# Prototype1.net
KiCad netlist of a schematic drawn in EAGLE
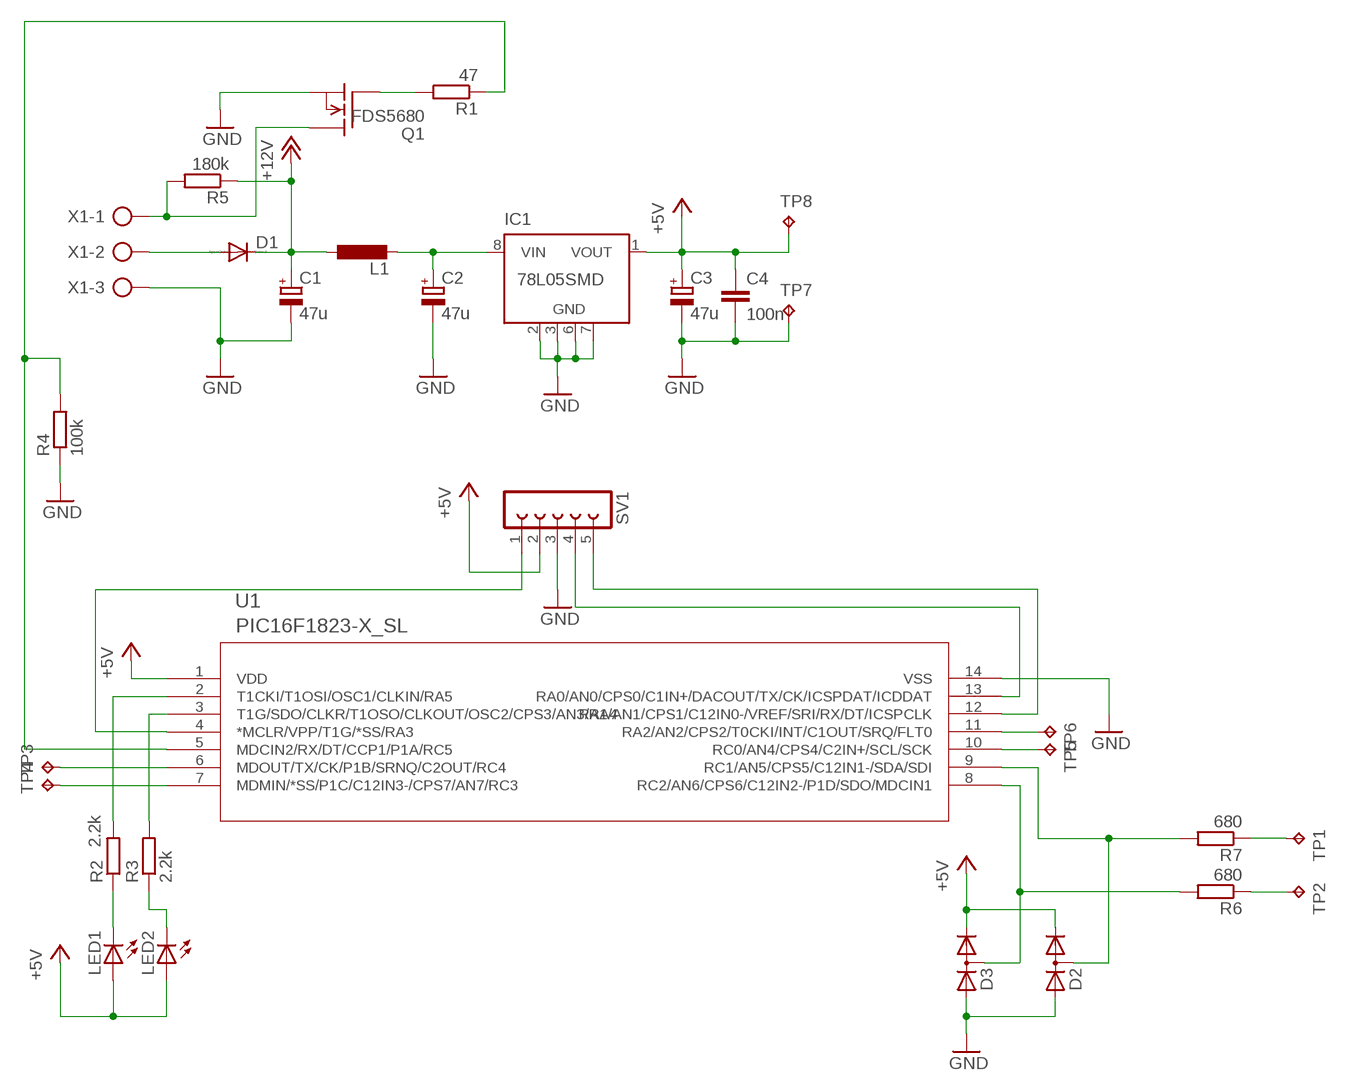
[diagram p0: schematic, sheet 1]

(export (version "E")
  (design (tool "Eeschema 10.0.6"))
  (components
    (comp (ref "C1")
      (value "47u")
      (footprint "eagle-import:153CLV-0605")
      (libsource (lib "eagle-import") (part "CPOL-EU153CLV-0605"))
    )
    (comp (ref "C2")
      (value "47u")
      (footprint "eagle-import:153CLV-0605")
      (libsource (lib "eagle-import") (part "CPOL-EU153CLV-0605"))
    )
    (comp (ref "C3")
      (value "47u")
      (footprint "eagle-import:153CLV-0605")
      (libsource (lib "eagle-import") (part "CPOL-EU153CLV-0605"))
    )
    (comp (ref "C4")
      (value "100n")
      (footprint "eagle-import:C0805")
      (libsource (lib "eagle-import") (part "C-EUC0805"))
    )
    (comp (ref "D1")
      (value "DIODE-MELF-MLL41")
      (footprint "eagle-import:MELF-MLL41")
      (libsource (lib "eagle-import") (part "DIODE-MELF-MLL41"))
    )
    (comp (ref "D2")
      (value "DIODE_2CACA-SOT23")
      (footprint "eagle-import:SOT23")
      (libsource (lib "eagle-import") (part "DIODE_2CACA-SOT23"))
    )
    (comp (ref "D3")
      (value "DIODE_2CACA-SOT23")
      (footprint "eagle-import:SOT23")
      (libsource (lib "eagle-import") (part "DIODE_2CACA-SOT23"))
    )
    (comp (ref "IC1")
      (value "78L05SMD")
      (footprint "eagle-import:SO08")
      (libsource (lib "eagle-import") (part "78LSMD05"))
    )
    (comp (ref "L1")
      (value "L-EUL3230M")
      (footprint "eagle-import:L3230M")
      (libsource (lib "eagle-import") (part "L-EUL3230M"))
    )
    (comp (ref "LED1")
      (value "LEDSML1206")
      (footprint "eagle-import:SML1206")
      (libsource (lib "eagle-import") (part "LEDSML1206"))
    )
    (comp (ref "LED2")
      (value "LEDSML1206")
      (footprint "eagle-import:SML1206")
      (libsource (lib "eagle-import") (part "LEDSML1206"))
    )
    (comp (ref "Q1")
      (value "FDS5680")
      (footprint "eagle-import:SO-8")
      (libsource (lib "eagle-import") (part "FDS5680"))
    )
    (comp (ref "R1")
      (value "47")
      (footprint "eagle-import:M1206")
      (libsource (lib "eagle-import") (part "R-EU_M1206"))
    )
    (comp (ref "R2")
      (value "2.2k")
      (footprint "eagle-import:M1206")
      (libsource (lib "eagle-import") (part "R-EU_M1206"))
    )
    (comp (ref "R3")
      (value "2.2k")
      (footprint "eagle-import:M1206")
      (libsource (lib "eagle-import") (part "R-EU_M1206"))
    )
    (comp (ref "R4")
      (value "100k")
      (footprint "eagle-import:M1206")
      (libsource (lib "eagle-import") (part "R-EU_M1206"))
    )
    (comp (ref "R5")
      (value "180k")
      (footprint "eagle-import:M1206")
      (libsource (lib "eagle-import") (part "R-EU_M1206"))
    )
    (comp (ref "R6")
      (value "680")
      (footprint "eagle-import:M1206")
      (libsource (lib "eagle-import") (part "R-EU_M1206"))
    )
    (comp (ref "R7")
      (value "680")
      (footprint "eagle-import:M1206")
      (libsource (lib "eagle-import") (part "R-EU_M1206"))
    )
    (comp (ref "SV1")
      (value "FE05-1")
      (footprint "eagle-import:FE05-1")
      (libsource (lib "eagle-import") (part "FE05-1"))
    )
    (comp (ref "TP1")
      (value "TPPAD1-13Y")
      (footprint "eagle-import:P1-13Y")
      (libsource (lib "eagle-import") (part "TPPAD1-13Y"))
    )
    (comp (ref "TP2")
      (value "TPPAD1-13Y")
      (footprint "eagle-import:P1-13Y")
      (libsource (lib "eagle-import") (part "TPPAD1-13Y"))
    )
    (comp (ref "TP3")
      (value "TPB2,54")
      (footprint "eagle-import:B2,54")
      (libsource (lib "eagle-import") (part "TPB2,54"))
    )
    (comp (ref "TP4")
      (value "TPB2,54")
      (footprint "eagle-import:B2,54")
      (libsource (lib "eagle-import") (part "TPB2,54"))
    )
    (comp (ref "TP5")
      (value "TPB2,54")
      (footprint "eagle-import:B2,54")
      (libsource (lib "eagle-import") (part "TPB2,54"))
    )
    (comp (ref "TP6")
      (value "TPB2,54")
      (footprint "eagle-import:B2,54")
      (libsource (lib "eagle-import") (part "TPB2,54"))
    )
    (comp (ref "TP7")
      (value "TPB2,54")
      (footprint "eagle-import:B2,54")
      (libsource (lib "eagle-import") (part "TPB2,54"))
    )
    (comp (ref "TP8")
      (value "TPB2,54")
      (footprint "eagle-import:B2,54")
      (libsource (lib "eagle-import") (part "TPB2,54"))
    )
    (comp (ref "U1")
      (value "PIC16F1823-X_SL")
      (footprint "eagle-import:SOIC14-N_MC")
      (libsource (lib "eagle-import") (part "PIC16F1823-X_SL"))
    )
    (comp (ref "X1")
      (value "AK500/3")
      (footprint "eagle-import:AK500_3")
      (libsource (lib "eagle-import") (part "AK500/3"))
    )
  )
  (nets
    (net (code "1") (name "+5V") (class "Default")
      (node (ref "C3") (pin "+") (pinfunction "+_+") (pintype "passive"))
      (node (ref "C4") (pin "1") (pinfunction "1_1") (pintype "passive"))
      (node (ref "D2") (pin "2") (pinfunction "C_2") (pintype "passive"))
      (node (ref "D3") (pin "2") (pinfunction "C_2") (pintype "passive"))
      (node (ref "IC1") (pin "1") (pinfunction "VOUT_1") (pintype "output"))
      (node (ref "LED1") (pin "A") (pinfunction "A_A") (pintype "passive"))
      (node (ref "LED2") (pin "A") (pinfunction "A_A") (pintype "passive"))
      (node (ref "SV1") (pin "2") (pinfunction "2_2") (pintype "passive"))
      (node (ref "TP8") (pin "TP") (pinfunction "TP_TP") (pintype "input"))
      (node (ref "U1") (pin "1") (pinfunction "VDD_1") (pintype "power_in"))
    )
    (net (code "2") (name "+12V") (class "Default")
      (node (ref "C1") (pin "+") (pinfunction "+_+") (pintype "passive"))
      (node (ref "D1") (pin "C") (pinfunction "C_C") (pintype "passive"))
      (node (ref "L1") (pin "1") (pinfunction "1_1") (pintype "passive"))
      (node (ref "R5") (pin "1") (pinfunction "1_1") (pintype "passive"))
    )
    (net (code "3") (name "GND") (class "Default")
      (node (ref "C1") (pin "-") (pinfunction "-_-") (pintype "passive"))
      (node (ref "C2") (pin "-") (pinfunction "-_-") (pintype "passive"))
      (node (ref "C3") (pin "-") (pinfunction "-_-") (pintype "passive"))
      (node (ref "C4") (pin "2") (pinfunction "2_2") (pintype "passive"))
      (node (ref "D2") (pin "1") (pinfunction "A_1") (pintype "passive"))
      (node (ref "D3") (pin "1") (pinfunction "A_1") (pintype "passive"))
      (node (ref "IC1") (pin "2") (pinfunction "GND_2") (pintype "power_in"))
      (node (ref "IC1") (pin "3") (pinfunction "GND_3") (pintype "power_in"))
      (node (ref "IC1") (pin "6") (pinfunction "GND_6") (pintype "power_in"))
      (node (ref "IC1") (pin "7") (pinfunction "GND_7") (pintype "power_in"))
      (node (ref "Q1") (pin "1") (pinfunction "S_1") (pintype "passive"))
      (node (ref "Q1") (pin "2") (pinfunction "S_2") (pintype "passive"))
      (node (ref "Q1") (pin "3") (pinfunction "S_3") (pintype "passive"))
      (node (ref "R4") (pin "1") (pinfunction "1_1") (pintype "passive"))
      (node (ref "SV1") (pin "3") (pinfunction "3_3") (pintype "passive"))
      (node (ref "TP7") (pin "TP") (pinfunction "TP_TP") (pintype "input"))
      (node (ref "U1") (pin "14") (pinfunction "VSS_14") (pintype "power_in"))
      (node (ref "X1") (pin "3") (pinfunction "KL_3") (pintype "passive"))
    )
    (net (code "4") (name "Net-(D2-AC)") (class "Default")
      (node (ref "D2") (pin "3") (pinfunction "AC_3") (pintype "passive"))
      (node (ref "R7") (pin "2") (pinfunction "2_2") (pintype "passive"))
      (node (ref "U1") (pin "9") (pinfunction "RC1/AN5/CPS5/C12IN1-/SDA/SDI_9") (pintype "bidirectional"))
    )
    (net (code "5") (name "Net-(D3-AC)") (class "Default")
      (node (ref "D3") (pin "3") (pinfunction "AC_3") (pintype "passive"))
      (node (ref "R6") (pin "2") (pinfunction "2_2") (pintype "passive"))
      (node (ref "U1") (pin "8") (pinfunction "RC2/AN6/CPS6/C12IN2-/P1D/SDO/MDCIN1_8") (pintype "bidirectional"))
    )
    (net (code "6") (name "Net-(IC1A-VIN)") (class "Default")
      (node (ref "C2") (pin "+") (pinfunction "+_+") (pintype "passive"))
      (node (ref "IC1") (pin "8") (pinfunction "VIN_8") (pintype "passive"))
      (node (ref "L1") (pin "2") (pinfunction "2_2") (pintype "passive"))
    )
    (net (code "7") (name "Net-(LED1-PadC)") (class "Default")
      (node (ref "LED1") (pin "C") (pinfunction "C_C") (pintype "passive"))
      (node (ref "R2") (pin "1") (pinfunction "1_1") (pintype "passive"))
    )
    (net (code "8") (name "Net-(LED2-PadC)") (class "Default")
      (node (ref "LED2") (pin "C") (pinfunction "C_C") (pintype "passive"))
      (node (ref "R3") (pin "1") (pinfunction "1_1") (pintype "passive"))
    )
    (net (code "9") (name "Net-(Q1-G)") (class "Default")
      (node (ref "Q1") (pin "4") (pinfunction "G_4") (pintype "passive"))
      (node (ref "R1") (pin "2") (pinfunction "2_2") (pintype "passive"))
    )
    (net (code "10") (name "Net-(R6-Pad1)") (class "Default")
      (node (ref "R6") (pin "1") (pinfunction "1_1") (pintype "passive"))
      (node (ref "TP2") (pin "TP") (pinfunction "TP_TP") (pintype "input"))
    )
    (net (code "11") (name "Net-(R7-Pad1)") (class "Default")
      (node (ref "R7") (pin "1") (pinfunction "1_1") (pintype "passive"))
      (node (ref "TP1") (pin "TP") (pinfunction "TP_TP") (pintype "input"))
    )
    (net (code "12") (name "Net-(U1-*MCLR{slash}VPP{slash}T1G{slash}*SS{slash}RA3)") (class "Default")
      (node (ref "SV1") (pin "1") (pinfunction "1_1") (pintype "passive"))
      (node (ref "U1") (pin "4") (pinfunction "*MCLR/VPP/T1G/*SS/RA3_4") (pintype "bidirectional"))
    )
    (net (code "13") (name "Net-(U1-MDCIN2{slash}RX{slash}DT{slash}CCP1{slash}P1A{slash}RC5)") (class "Default")
      (node (ref "R1") (pin "1") (pinfunction "1_1") (pintype "passive"))
      (node (ref "R4") (pin "2") (pinfunction "2_2") (pintype "passive"))
      (node (ref "U1") (pin "5") (pinfunction "MDCIN2/RX/DT/CCP1/P1A/RC5_5") (pintype "bidirectional"))
    )
    (net (code "14") (name "Net-(U1-MDMIN{slash}*SS{slash}P1C{slash}C12IN3-{slash}CPS7{slash}AN7{slash}RC3)") (class "Default")
      (node (ref "TP4") (pin "TP") (pinfunction "TP_TP") (pintype "input"))
      (node (ref "U1") (pin "7") (pinfunction "MDMIN/*SS/P1C/C12IN3-/CPS7/AN7/RC3_7") (pintype "bidirectional"))
    )
    (net (code "15") (name "Net-(U1-MDOUT{slash}TX{slash}CK{slash}P1B{slash}SRNQ{slash}C2OUT{slash}RC4)") (class "Default")
      (node (ref "TP3") (pin "TP") (pinfunction "TP_TP") (pintype "input"))
      (node (ref "U1") (pin "6") (pinfunction "MDOUT/TX/CK/P1B/SRNQ/C2OUT/RC4_6") (pintype "bidirectional"))
    )
    (net (code "16") (name "Net-(U1-RA0{slash}AN0{slash}CPS0{slash}C1IN+{slash}DACOUT{slash}TX{slash}CK{slash}ICSPDAT{slash}ICDDAT)") (class "Default")
      (node (ref "SV1") (pin "4") (pinfunction "4_4") (pintype "passive"))
      (node (ref "U1") (pin "13") (pinfunction "RA0/AN0/CPS0/C1IN+/DACOUT/TX/CK/ICSPDAT/ICDDAT_13") (pintype "bidirectional"))
    )
    (net (code "17") (name "Net-(U1-RA1{slash}AN1{slash}CPS1{slash}C12IN0-{slash}VREF{slash}SRI{slash}RX{slash}DT{slash}ICSPCLK)") (class "Default")
      (node (ref "SV1") (pin "5") (pinfunction "5_5") (pintype "passive"))
      (node (ref "U1") (pin "12") (pinfunction "RA1/AN1/CPS1/C12IN0-/VREF/SRI/RX/DT/ICSPCLK_12") (pintype "bidirectional"))
    )
    (net (code "18") (name "Net-(U1-RA2{slash}AN2{slash}CPS2{slash}T0CKI{slash}INT{slash}C1OUT{slash}SRQ{slash}FLT0)") (class "Default")
      (node (ref "TP6") (pin "TP") (pinfunction "TP_TP") (pintype "input"))
      (node (ref "U1") (pin "11") (pinfunction "RA2/AN2/CPS2/T0CKI/INT/C1OUT/SRQ/FLT0_11") (pintype "bidirectional"))
    )
    (net (code "19") (name "Net-(U1-RC0{slash}AN4{slash}CPS4{slash}C2IN+{slash}SCL{slash}SCK)") (class "Default")
      (node (ref "TP5") (pin "TP") (pinfunction "TP_TP") (pintype "input"))
      (node (ref "U1") (pin "10") (pinfunction "RC0/AN4/CPS4/C2IN+/SCL/SCK_10") (pintype "bidirectional"))
    )
    (net (code "20") (name "Net-(U1-T1CKI{slash}T1OSI{slash}OSC1{slash}CLKIN{slash}RA5)") (class "Default")
      (node (ref "R2") (pin "2") (pinfunction "2_2") (pintype "passive"))
      (node (ref "U1") (pin "2") (pinfunction "T1CKI/T1OSI/OSC1/CLKIN/RA5_2") (pintype "bidirectional"))
    )
    (net (code "21") (name "Net-(U1-T1G{slash}SDO{slash}CLKR{slash}T1OSO{slash}CLKOUT{slash}OSC2{slash}CPS3{slash}AN3{slash}RA4)") (class "Default")
      (node (ref "R3") (pin "2") (pinfunction "2_2") (pintype "passive"))
      (node (ref "U1") (pin "3") (pinfunction "T1G/SDO/CLKR/T1OSO/CLKOUT/OSC2/CPS3/AN3/RA4_3") (pintype "bidirectional"))
    )
    (net (code "22") (name "Net-(X1A-KL)") (class "Default")
      (node (ref "Q1") (pin "5") (pinfunction "D_5") (pintype "passive"))
      (node (ref "Q1") (pin "6") (pinfunction "D_6") (pintype "passive"))
      (node (ref "Q1") (pin "7") (pinfunction "D_7") (pintype "passive"))
      (node (ref "Q1") (pin "8") (pinfunction "D_8") (pintype "passive"))
      (node (ref "R5") (pin "2") (pinfunction "2_2") (pintype "passive"))
      (node (ref "X1") (pin "1") (pinfunction "KL_1") (pintype "passive"))
    )
    (net (code "23") (name "Net-(X1B-KL)") (class "Default")
      (node (ref "D1") (pin "A") (pinfunction "A_A") (pintype "passive"))
      (node (ref "X1") (pin "2") (pinfunction "KL_2") (pintype "passive"))
    )
  )
)
